# LEVEL_TRANSLATORS.net
KiCad netlist of a schematic drawn in Altium Designer
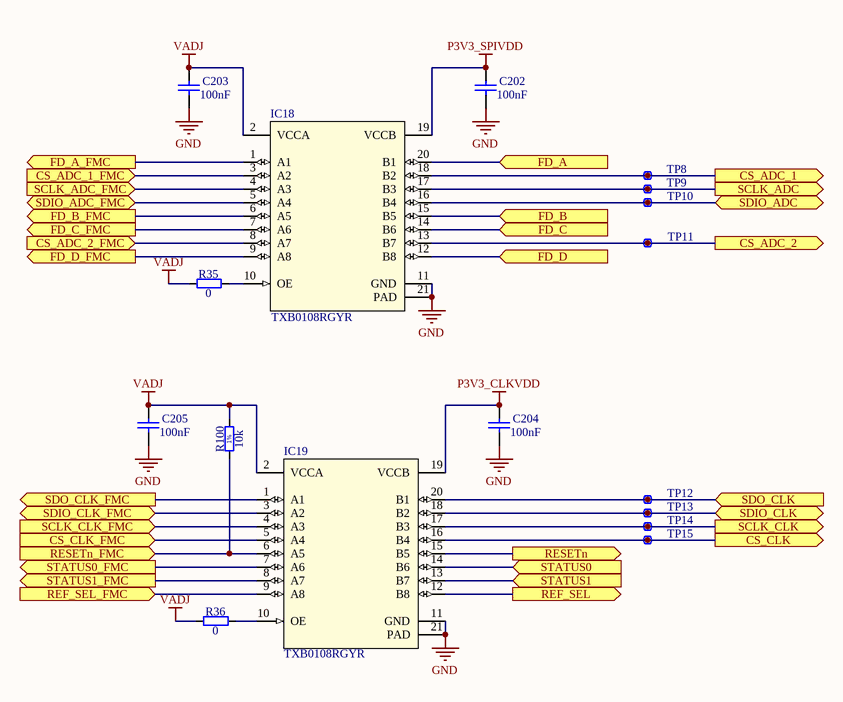
[diagram p0: LEVEL_TRANSLATORS.SchDoc]

(export (version "E")
  (design (tool "Eeschema 10.0.6"))
  (components
    (comp (ref "C202")
      (value "100nF")
      (footprint "CAPC0603X33N")
      (description "Non-polarised capacitor")
      (fields
        (field (name "TOLERANCE") "±10%")
        (field (name "PART NUMBER") "CC0201_100NF_6.3V_10%_X5R")
        (field (name "AUTHOR") "CERN DEM JLC")
      )
      (libsource (lib "Capacitors") (part "Capacitor - non polarized"))
    )
    (comp (ref "C203")
      (value "100nF")
      (footprint "CAPC0603X33N")
      (description "Non-polarised capacitor")
      (fields
        (field (name "TOLERANCE") "±10%")
        (field (name "PART NUMBER") "CC0201_100NF_6.3V_10%_X5R")
        (field (name "AUTHOR") "CERN DEM JLC")
      )
      (libsource (lib "Capacitors") (part "Capacitor - non polarized"))
    )
    (comp (ref "C204")
      (value "100nF")
      (footprint "CAPC0603X33N")
      (description "Non-polarised capacitor")
      (fields
        (field (name "TOLERANCE") "±10%")
        (field (name "PART NUMBER") "CC0201_100NF_6.3V_10%_X5R")
        (field (name "AUTHOR") "CERN DEM JLC")
      )
      (libsource (lib "Capacitors") (part "Capacitor - non polarized"))
    )
    (comp (ref "C205")
      (value "100nF")
      (footprint "CAPC0603X33N")
      (description "Non-polarised capacitor")
      (fields
        (field (name "TOLERANCE") "±10%")
        (field (name "PART NUMBER") "CC0201_100NF_6.3V_10%_X5R")
        (field (name "AUTHOR") "CERN DEM JLC")
      )
      (libsource (lib "Capacitors") (part "Capacitor - non polarized"))
    )
    (comp (ref "IC18")
      (value "TXB0108RGYR")
      (footprint "RGY20_3P05x2P05")
      (description "8-Bit Bidirectional Voltage-Level Translator with Auto-Direction Sensing")
      (fields (field (name "MANUFACTURER") "Texas Instruments"))
      (libsource (lib "FMC_ADC") (part "TXB0108RGYR"))
    )
    (comp (ref "IC19")
      (value "TXB0108RGYR")
      (footprint "RGY20_3P05x2P05")
      (description "8-Bit Bidirectional Voltage-Level Translator with Auto-Direction Sensing")
      (fields (field (name "MANUFACTURER") "Texas Instruments"))
      (libsource (lib "FMC_ADC") (part "TXB0108RGYR"))
    )
    (comp (ref "R35")
      (value "0")
      (footprint "RESC1005X40N")
      (description "Resistor")
      (fields
        (field (name "PART NUMBER") "R0402_0R_JUMPER")
        (field (name "MANUFACTURER") "GENERIC")
        (field (name "AUTHOR") "CERN DEM JLC")
      )
      (libsource (lib "Resistors") (part "Resistor"))
    )
    (comp (ref "R36")
      (value "0")
      (footprint "RESC1005X40N")
      (description "Resistor")
      (fields
        (field (name "PART NUMBER") "R0402_0R_JUMPER")
        (field (name "MANUFACTURER") "GENERIC")
        (field (name "AUTHOR") "CERN DEM JLC")
      )
      (libsource (lib "Resistors") (part "Resistor"))
    )
    (comp (ref "R100")
      (value "10k")
      (footprint "RESC1005X40N")
      (description "Resistor - 1%")
      (fields
        (field (name "PART NUMBER") "R0402_10K_1%_0.0625W_100PPM")
        (field (name "POWER") "0.0625W")
        (field (name "AUTHOR") "CERN DEM JLC")
      )
      (libsource (lib "Resistors") (part "Resistor - 1%"))
    )
    (comp (ref "TP8")
      (value "Test Point")
      (footprint "TPS62")
      (fields (field (name "PART NUMBER") "SMD_PAD_0.62X0.62MM") (field (name "AUTHOR") "CERN DEM JLC"))
      (libsource (lib "FMC_ADC") (part "Test Point"))
    )
    (comp (ref "TP9")
      (value "Test Point")
      (footprint "TPS62")
      (fields (field (name "PART NUMBER") "SMD_PAD_0.62X0.62MM") (field (name "AUTHOR") "CERN DEM JLC"))
      (libsource (lib "FMC_ADC") (part "Test Point"))
    )
    (comp (ref "TP10")
      (value "Test Point")
      (footprint "TPS62")
      (fields (field (name "PART NUMBER") "SMD_PAD_0.62X0.62MM") (field (name "AUTHOR") "CERN DEM JLC"))
      (libsource (lib "FMC_ADC") (part "Test Point"))
    )
    (comp (ref "TP11")
      (value "Test Point")
      (footprint "TPS62")
      (fields (field (name "PART NUMBER") "SMD_PAD_0.62X0.62MM") (field (name "AUTHOR") "CERN DEM JLC"))
      (libsource (lib "FMC_ADC") (part "Test Point"))
    )
    (comp (ref "TP12")
      (value "Test Point")
      (footprint "TPS62")
      (fields (field (name "PART NUMBER") "SMD_PAD_0.62X0.62MM") (field (name "AUTHOR") "CERN DEM JLC"))
      (libsource (lib "FMC_ADC") (part "Test Point"))
    )
    (comp (ref "TP13")
      (value "Test Point")
      (footprint "TPS62")
      (fields (field (name "PART NUMBER") "SMD_PAD_0.62X0.62MM") (field (name "AUTHOR") "CERN DEM JLC"))
      (libsource (lib "FMC_ADC") (part "Test Point"))
    )
    (comp (ref "TP14")
      (value "Test Point")
      (footprint "TPS62")
      (fields (field (name "PART NUMBER") "SMD_PAD_0.62X0.62MM") (field (name "AUTHOR") "CERN DEM JLC"))
      (libsource (lib "FMC_ADC") (part "Test Point"))
    )
    (comp (ref "TP15")
      (value "Test Point")
      (footprint "TPS62")
      (fields (field (name "PART NUMBER") "SMD_PAD_0.62X0.62MM") (field (name "AUTHOR") "CERN DEM JLC"))
      (libsource (lib "FMC_ADC") (part "Test Point"))
    )
  )
  (nets
    (net (code "1") (name "/CS_ADC_1") (class "Default")
      (node (ref "IC18") (pin "18") (pinfunction "B2_18") (pintype "bidirectional"))
      (node (ref "TP8") (pin "1") (pinfunction "1_1") (pintype "bidirectional"))
    )
    (net (code "2") (name "/CS_ADC_1_FMC") (class "Default")
      (node (ref "IC18") (pin "3") (pinfunction "A2_3") (pintype "bidirectional"))
    )
    (net (code "3") (name "/CS_ADC_2") (class "Default")
      (node (ref "IC18") (pin "13") (pinfunction "B7_13") (pintype "bidirectional"))
      (node (ref "TP11") (pin "1") (pinfunction "1_1") (pintype "bidirectional"))
    )
    (net (code "4") (name "/CS_ADC_2_FMC") (class "Default")
      (node (ref "IC18") (pin "8") (pinfunction "A7_8") (pintype "bidirectional"))
    )
    (net (code "5") (name "/CS_CLK") (class "Default")
      (node (ref "IC19") (pin "16") (pinfunction "B4_16") (pintype "bidirectional"))
      (node (ref "TP15") (pin "1") (pinfunction "1_1") (pintype "bidirectional"))
    )
    (net (code "6") (name "/CS_CLK_FMC") (class "Default")
      (node (ref "IC19") (pin "5") (pinfunction "A4_5") (pintype "bidirectional"))
    )
    (net (code "7") (name "/FD_A") (class "Default")
      (node (ref "IC18") (pin "20") (pinfunction "B1_20") (pintype "bidirectional"))
    )
    (net (code "8") (name "/FD_A_FMC") (class "Default")
      (node (ref "IC18") (pin "1") (pinfunction "A1_1") (pintype "bidirectional"))
    )
    (net (code "9") (name "/FD_B") (class "Default")
      (node (ref "IC18") (pin "15") (pinfunction "B5_15") (pintype "bidirectional"))
    )
    (net (code "10") (name "/FD_B_FMC") (class "Default")
      (node (ref "IC18") (pin "6") (pinfunction "A5_6") (pintype "bidirectional"))
    )
    (net (code "11") (name "/FD_C") (class "Default")
      (node (ref "IC18") (pin "14") (pinfunction "B6_14") (pintype "bidirectional"))
    )
    (net (code "12") (name "/FD_C_FMC") (class "Default")
      (node (ref "IC18") (pin "7") (pinfunction "A6_7") (pintype "bidirectional"))
    )
    (net (code "13") (name "/FD_D") (class "Default")
      (node (ref "IC18") (pin "12") (pinfunction "B8_12") (pintype "bidirectional"))
    )
    (net (code "14") (name "/FD_D_FMC") (class "Default")
      (node (ref "IC18") (pin "9") (pinfunction "A8_9") (pintype "bidirectional"))
    )
    (net (code "15") (name "/REF_SEL") (class "Default")
      (node (ref "IC19") (pin "12") (pinfunction "B8_12") (pintype "bidirectional"))
    )
    (net (code "16") (name "/REF_SEL_FMC") (class "Default")
      (node (ref "IC19") (pin "9") (pinfunction "A8_9") (pintype "bidirectional"))
    )
    (net (code "17") (name "/RESETn") (class "Default")
      (node (ref "IC19") (pin "15") (pinfunction "B5_15") (pintype "bidirectional"))
    )
    (net (code "18") (name "/RESETn_FMC") (class "Default")
      (node (ref "IC19") (pin "6") (pinfunction "A5_6") (pintype "bidirectional"))
      (node (ref "R100") (pin "1") (pinfunction "1_1") (pintype "passive"))
    )
    (net (code "19") (name "/SCLK_ADC") (class "Default")
      (node (ref "IC18") (pin "17") (pinfunction "B3_17") (pintype "bidirectional"))
      (node (ref "TP9") (pin "1") (pinfunction "1_1") (pintype "bidirectional"))
    )
    (net (code "20") (name "/SCLK_ADC_FMC") (class "Default")
      (node (ref "IC18") (pin "4") (pinfunction "A3_4") (pintype "bidirectional"))
    )
    (net (code "21") (name "/SCLK_CLK") (class "Default")
      (node (ref "IC19") (pin "17") (pinfunction "B3_17") (pintype "bidirectional"))
      (node (ref "TP14") (pin "1") (pinfunction "1_1") (pintype "bidirectional"))
    )
    (net (code "22") (name "/SCLK_CLK_FMC") (class "Default")
      (node (ref "IC19") (pin "4") (pinfunction "A3_4") (pintype "bidirectional"))
    )
    (net (code "23") (name "/SDIO_ADC") (class "Default")
      (node (ref "IC18") (pin "16") (pinfunction "B4_16") (pintype "bidirectional"))
      (node (ref "TP10") (pin "1") (pinfunction "1_1") (pintype "bidirectional"))
    )
    (net (code "24") (name "/SDIO_ADC_FMC") (class "Default")
      (node (ref "IC18") (pin "5") (pinfunction "A4_5") (pintype "bidirectional"))
    )
    (net (code "25") (name "/SDIO_CLK") (class "Default")
      (node (ref "IC19") (pin "18") (pinfunction "B2_18") (pintype "bidirectional"))
      (node (ref "TP13") (pin "1") (pinfunction "1_1") (pintype "bidirectional"))
    )
    (net (code "26") (name "/SDIO_CLK_FMC") (class "Default")
      (node (ref "IC19") (pin "3") (pinfunction "A2_3") (pintype "bidirectional"))
    )
    (net (code "27") (name "/SDO_CLK") (class "Default")
      (node (ref "IC19") (pin "20") (pinfunction "B1_20") (pintype "bidirectional"))
      (node (ref "TP12") (pin "1") (pinfunction "1_1") (pintype "bidirectional"))
    )
    (net (code "28") (name "/SDO_CLK_FMC") (class "Default")
      (node (ref "IC19") (pin "1") (pinfunction "A1_1") (pintype "bidirectional"))
    )
    (net (code "29") (name "/STATUS0") (class "Default")
      (node (ref "IC19") (pin "14") (pinfunction "B6_14") (pintype "bidirectional"))
    )
    (net (code "30") (name "/STATUS0_FMC") (class "Default")
      (node (ref "IC19") (pin "7") (pinfunction "A6_7") (pintype "bidirectional"))
    )
    (net (code "31") (name "/STATUS1") (class "Default")
      (node (ref "IC19") (pin "13") (pinfunction "B7_13") (pintype "bidirectional"))
    )
    (net (code "32") (name "/STATUS1_FMC") (class "Default")
      (node (ref "IC19") (pin "8") (pinfunction "A7_8") (pintype "bidirectional"))
    )
    (net (code "33") (name "GND") (class "Default")
      (node (ref "C202") (pin "1") (pinfunction "1_1") (pintype "passive"))
      (node (ref "C203") (pin "1") (pinfunction "1_1") (pintype "passive"))
      (node (ref "C204") (pin "1") (pinfunction "1_1") (pintype "passive"))
      (node (ref "C205") (pin "1") (pinfunction "1_1") (pintype "passive"))
      (node (ref "IC18") (pin "11") (pinfunction "GND_11") (pintype "power_in"))
      (node (ref "IC18") (pin "21") (pinfunction "PAD_21") (pintype "power_in"))
      (node (ref "IC19") (pin "11") (pinfunction "GND_11") (pintype "power_in"))
      (node (ref "IC19") (pin "21") (pinfunction "PAD_21") (pintype "power_in"))
    )
    (net (code "34") (name "Net-(IC18-OE)") (class "Default")
      (node (ref "IC18") (pin "10") (pinfunction "OE_10") (pintype "input"))
      (node (ref "R35") (pin "2") (pinfunction "2_2") (pintype "passive"))
    )
    (net (code "35") (name "Net-(IC19-OE)") (class "Default")
      (node (ref "IC19") (pin "10") (pinfunction "OE_10") (pintype "input"))
      (node (ref "R36") (pin "2") (pinfunction "2_2") (pintype "passive"))
    )
    (net (code "36") (name "P3V3_CLKVDD") (class "Default")
      (node (ref "C204") (pin "2") (pinfunction "2_2") (pintype "passive"))
      (node (ref "IC19") (pin "19") (pinfunction "VCCB_19") (pintype "power_in"))
    )
    (net (code "37") (name "P3V3_SPIVDD") (class "Default")
      (node (ref "C202") (pin "2") (pinfunction "2_2") (pintype "passive"))
      (node (ref "IC18") (pin "19") (pinfunction "VCCB_19") (pintype "power_in"))
    )
    (net (code "38") (name "VADJ") (class "Default")
      (node (ref "C203") (pin "2") (pinfunction "2_2") (pintype "passive"))
      (node (ref "C205") (pin "2") (pinfunction "2_2") (pintype "passive"))
      (node (ref "IC18") (pin "2") (pinfunction "VCCA_2") (pintype "power_in"))
      (node (ref "IC19") (pin "2") (pinfunction "VCCA_2") (pintype "power_in"))
      (node (ref "R100") (pin "2") (pinfunction "2_2") (pintype "passive"))
      (node (ref "R35") (pin "1") (pinfunction "1_1") (pintype "passive"))
      (node (ref "R36") (pin "1") (pinfunction "1_1") (pintype "passive"))
    )
  )
)
